# circuit.net
KiCad netlist of a schematic drawn in EAGLE
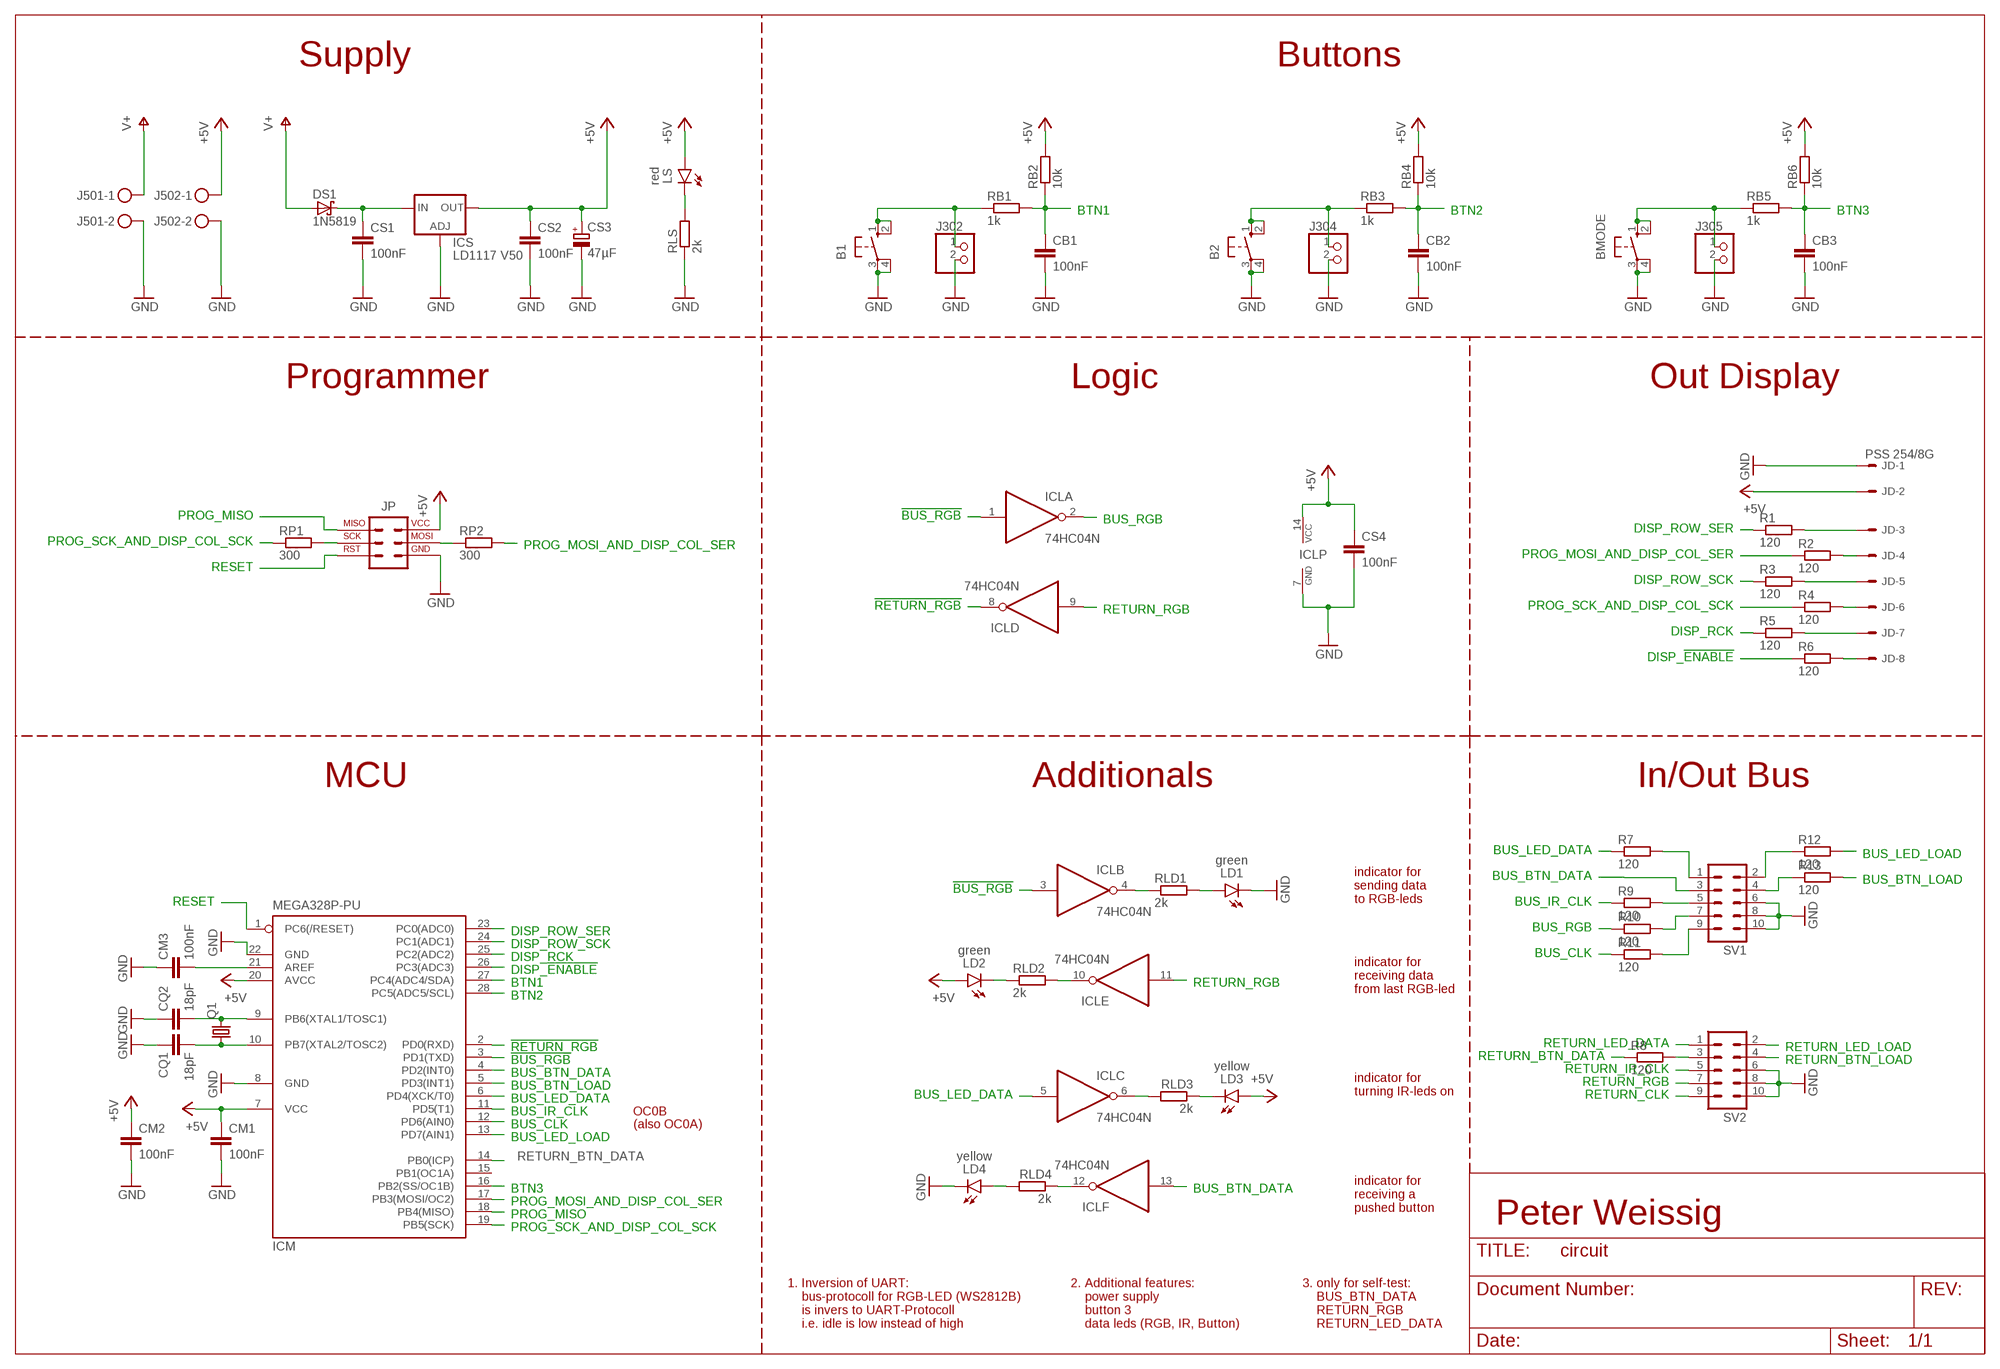
[diagram p0: schematic, sheet 1]

(export (version "E")
  (design (tool "Eeschema 10.0.6"))
  (components
    (comp (ref "B1")
      (value "10-XX")
      (footprint "eagle-import:B3F-10XX")
      (fields (field (name "MPN") "B3F-1000"))
      (libsource (lib "eagle-import") (part "10-XX"))
    )
    (comp (ref "B2")
      (value "10-XX")
      (footprint "eagle-import:B3F-10XX")
      (fields (field (name "MPN") "B3F-1000"))
      (libsource (lib "eagle-import") (part "10-XX"))
    )
    (comp (ref "BMODE")
      (value "10-XX")
      (footprint "eagle-import:B3F-10XX")
      (fields (field (name "MPN") "B3F-1000"))
      (libsource (lib "eagle-import") (part "10-XX"))
    )
    (comp (ref "CB1")
      (value "100nF")
      (footprint "eagle-import:C025-025X050")
      (libsource (lib "eagle-import") (part "C-EU025-025X050"))
    )
    (comp (ref "CB2")
      (value "100nF")
      (footprint "eagle-import:C025-025X050")
      (libsource (lib "eagle-import") (part "C-EU025-025X050"))
    )
    (comp (ref "CB3")
      (value "100nF")
      (footprint "eagle-import:C025-025X050")
      (libsource (lib "eagle-import") (part "C-EU025-025X050"))
    )
    (comp (ref "CM1")
      (value "100nF")
      (footprint "eagle-import:C025-025X050")
      (libsource (lib "eagle-import") (part "C-EU025-025X050"))
    )
    (comp (ref "CM2")
      (value "100nF")
      (footprint "eagle-import:C025-025X050")
      (libsource (lib "eagle-import") (part "C-EU025-025X050"))
    )
    (comp (ref "CM3")
      (value "100nF")
      (footprint "eagle-import:C025-025X050")
      (libsource (lib "eagle-import") (part "C-EU025-025X050"))
    )
    (comp (ref "CQ1")
      (value "18pF")
      (footprint "eagle-import:C025-025X050")
      (libsource (lib "eagle-import") (part "C-EU025-025X050"))
    )
    (comp (ref "CQ2")
      (value "18pF")
      (footprint "eagle-import:C025-025X050")
      (libsource (lib "eagle-import") (part "C-EU025-025X050"))
    )
    (comp (ref "CS1")
      (value "100nF")
      (footprint "eagle-import:C025-025X050")
      (libsource (lib "eagle-import") (part "C-EU025-025X050"))
    )
    (comp (ref "CS2")
      (value "100nF")
      (footprint "eagle-import:C025-025X050")
      (libsource (lib "eagle-import") (part "C-EU025-025X050"))
    )
    (comp (ref "CS3")
      (value "47µF")
      (footprint "eagle-import:E2-5")
      (libsource (lib "eagle-import") (part "CPOL-EUE2-5"))
    )
    (comp (ref "CS4")
      (value "100nF")
      (footprint "eagle-import:C025-025X050")
      (libsource (lib "eagle-import") (part "C-EU025-025X050"))
    )
    (comp (ref "DS1")
      (value "1N5819")
      (footprint "eagle-import:DO41-7.6")
      (libsource (lib "eagle-import") (part "1N5819-B"))
    )
    (comp (ref "ICL")
      (value "74HC04N")
      (footprint "eagle-import:DIL14")
      (libsource (lib "eagle-import") (part "7404NAC"))
    )
    (comp (ref "ICM")
      (value "MEGA328P-PU")
      (footprint "eagle-import:DIL28-3")
      (libsource (lib "eagle-import") (part "MEGA8-P"))
    )
    (comp (ref "ICS")
      (value "LD1117 V50")
      (footprint "eagle-import:TO220L1")
      (libsource (lib "eagle-import") (part "LD117A?V50"))
    )
    (comp (ref "J302")
      (value "PINHD-1X2")
      (footprint "eagle-import:1X02")
      (libsource (lib "eagle-import") (part "PINHD-1X2"))
    )
    (comp (ref "J304")
      (value "PINHD-1X2")
      (footprint "eagle-import:1X02")
      (libsource (lib "eagle-import") (part "PINHD-1X2"))
    )
    (comp (ref "J305")
      (value "PINHD-1X2")
      (footprint "eagle-import:1X02")
      (libsource (lib "eagle-import") (part "PINHD-1X2"))
    )
    (comp (ref "J501")
      (value "STECKER_SPG_2")
      (footprint "eagle-import:STECKER_SPG_2")
      (libsource (lib "eagle-import") (part "STECKER_SPG_2"))
    )
    (comp (ref "J502")
      (value "STECKER_SPG_2")
      (footprint "eagle-import:STECKER_SPG_2")
      (libsource (lib "eagle-import") (part "STECKER_SPG_2"))
    )
    (comp (ref "JD")
      (value "PSS 254/8G")
      (footprint "eagle-import:22-23-2081")
      (fields (field (name "MF") "MOLEX") (field (name "MPN") "22-23-2081"))
      (libsource (lib "eagle-import") (part "22-23-2081"))
    )
    (comp (ref "JP")
      (value "STECKER_ISP_6")
      (footprint "eagle-import:STECKER_WANNE_6")
      (libsource (lib "eagle-import") (part "STECKER_ISP_6"))
    )
    (comp (ref "LD1")
      (value "green")
      (footprint "eagle-import:LED_3MM")
      (libsource (lib "eagle-import") (part "LED-3MM"))
    )
    (comp (ref "LD2")
      (value "green")
      (footprint "eagle-import:LED_3MM")
      (libsource (lib "eagle-import") (part "LED-3MM"))
    )
    (comp (ref "LD3")
      (value "yellow")
      (footprint "eagle-import:LED_3MM")
      (libsource (lib "eagle-import") (part "LED-3MM"))
    )
    (comp (ref "LD4")
      (value "yellow")
      (footprint "eagle-import:LED_3MM")
      (libsource (lib "eagle-import") (part "LED-3MM"))
    )
    (comp (ref "LS")
      (value "red")
      (footprint "eagle-import:LED_3MM")
      (libsource (lib "eagle-import") (part "LED-3MM"))
    )
    (comp (ref "Q1")
      (value "CRYSTALHC49U70")
      (footprint "eagle-import:HC49U70")
      (libsource (lib "eagle-import") (part "CRYSTALHC49U70"))
    )
    (comp (ref "R1")
      (value "120")
      (footprint "eagle-import:R1206W")
      (libsource (lib "eagle-import") (part "R-EU_R1206W"))
    )
    (comp (ref "R2")
      (value "120")
      (footprint "eagle-import:R1206W")
      (libsource (lib "eagle-import") (part "R-EU_R1206W"))
    )
    (comp (ref "R3")
      (value "120")
      (footprint "eagle-import:R1206W")
      (libsource (lib "eagle-import") (part "R-EU_R1206W"))
    )
    (comp (ref "R4")
      (value "120")
      (footprint "eagle-import:R1206W")
      (libsource (lib "eagle-import") (part "R-EU_R1206W"))
    )
    (comp (ref "R5")
      (value "120")
      (footprint "eagle-import:R1206W")
      (libsource (lib "eagle-import") (part "R-EU_R1206W"))
    )
    (comp (ref "R6")
      (value "120")
      (footprint "eagle-import:R1206W")
      (libsource (lib "eagle-import") (part "R-EU_R1206W"))
    )
    (comp (ref "R7")
      (value "120")
      (footprint "eagle-import:R1206W")
      (libsource (lib "eagle-import") (part "R-EU_R1206W"))
    )
    (comp (ref "R8")
      (value "120")
      (footprint "eagle-import:R1206W")
      (libsource (lib "eagle-import") (part "R-EU_R1206W"))
    )
    (comp (ref "R9")
      (value "120")
      (footprint "eagle-import:R1206W")
      (libsource (lib "eagle-import") (part "R-EU_R1206W"))
    )
    (comp (ref "R10")
      (value "120")
      (footprint "eagle-import:R1206W")
      (libsource (lib "eagle-import") (part "R-EU_R1206W"))
    )
    (comp (ref "R11")
      (value "120")
      (footprint "eagle-import:R1206W")
      (libsource (lib "eagle-import") (part "R-EU_R1206W"))
    )
    (comp (ref "R12")
      (value "120")
      (footprint "eagle-import:R1206W")
      (libsource (lib "eagle-import") (part "R-EU_R1206W"))
    )
    (comp (ref "R13")
      (value "120")
      (footprint "eagle-import:R1206W")
      (libsource (lib "eagle-import") (part "R-EU_R1206W"))
    )
    (comp (ref "RB1")
      (value "1k")
      (footprint "eagle-import:0207_10")
      (libsource (lib "eagle-import") (part "R-EU_0207/10"))
    )
    (comp (ref "RB2")
      (value "10k")
      (footprint "eagle-import:0207_10")
      (libsource (lib "eagle-import") (part "R-EU_0207/10"))
    )
    (comp (ref "RB3")
      (value "1k")
      (footprint "eagle-import:0207_10")
      (libsource (lib "eagle-import") (part "R-EU_0207/10"))
    )
    (comp (ref "RB4")
      (value "10k")
      (footprint "eagle-import:0207_10")
      (libsource (lib "eagle-import") (part "R-EU_0207/10"))
    )
    (comp (ref "RB5")
      (value "1k")
      (footprint "eagle-import:0207_10")
      (libsource (lib "eagle-import") (part "R-EU_0207/10"))
    )
    (comp (ref "RB6")
      (value "10k")
      (footprint "eagle-import:0207_10")
      (libsource (lib "eagle-import") (part "R-EU_0207/10"))
    )
    (comp (ref "RLD1")
      (value "2k")
      (footprint "eagle-import:0207_10")
      (libsource (lib "eagle-import") (part "R-EU_0207/10"))
    )
    (comp (ref "RLD2")
      (value "2k")
      (footprint "eagle-import:0207_10")
      (libsource (lib "eagle-import") (part "R-EU_0207/10"))
    )
    (comp (ref "RLD3")
      (value "2k")
      (footprint "eagle-import:0207_10")
      (libsource (lib "eagle-import") (part "R-EU_0207/10"))
    )
    (comp (ref "RLD4")
      (value "2k")
      (footprint "eagle-import:0207_10")
      (libsource (lib "eagle-import") (part "R-EU_0207/10"))
    )
    (comp (ref "RLS")
      (value "2k")
      (footprint "eagle-import:0207_10")
      (libsource (lib "eagle-import") (part "R-EU_0207/10"))
    )
    (comp (ref "RP1")
      (value "300")
      (footprint "eagle-import:0207_10")
      (libsource (lib "eagle-import") (part "R-EU_0207/10"))
    )
    (comp (ref "RP2")
      (value "300")
      (footprint "eagle-import:0207_10")
      (libsource (lib "eagle-import") (part "R-EU_0207/10"))
    )
    (comp (ref "SV1")
      (value "ML10")
      (footprint "eagle-import:ML10")
      (libsource (lib "eagle-import") (part "ML10"))
    )
    (comp (ref "SV2")
      (value "ML10")
      (footprint "eagle-import:ML10")
      (libsource (lib "eagle-import") (part "ML10"))
    )
  )
  (nets
    (net (code "1") (name "+5V") (class "Default")
      (node (ref "CM1") (pin "1") (pinfunction "1_1") (pintype "passive"))
      (node (ref "CM2") (pin "1") (pinfunction "1_1") (pintype "passive"))
      (node (ref "CS2") (pin "1") (pinfunction "1_1") (pintype "passive"))
      (node (ref "CS3") (pin "+") (pinfunction "+_+") (pintype "passive"))
      (node (ref "CS4") (pin "1") (pinfunction "1_1") (pintype "passive"))
      (node (ref "ICL") (pin "14") (pinfunction "VCC_14") (pintype "power_in"))
      (node (ref "ICM") (pin "20") (pinfunction "AVCC_20") (pintype "power_in"))
      (node (ref "ICM") (pin "7") (pinfunction "VCC_7") (pintype "power_in"))
      (node (ref "ICS") (pin "2") (pinfunction "OUT_2") (pintype "passive"))
      (node (ref "J502") (pin "1") (pinfunction "KL_1") (pintype "passive"))
      (node (ref "JD") (pin "2") (pinfunction "S_2") (pintype "passive"))
      (node (ref "JP") (pin "2") (pinfunction "2_VCC_2") (pintype "passive"))
      (node (ref "LD2") (pin "A") (pinfunction "A_A") (pintype "passive"))
      (node (ref "LD3") (pin "A") (pinfunction "A_A") (pintype "passive"))
      (node (ref "LS") (pin "A") (pinfunction "A_A") (pintype "passive"))
      (node (ref "RB2") (pin "2") (pinfunction "2_2") (pintype "passive"))
      (node (ref "RB4") (pin "2") (pinfunction "2_2") (pintype "passive"))
      (node (ref "RB6") (pin "2") (pinfunction "2_2") (pintype "passive"))
    )
    (net (code "2") (name "/BTN1") (class "Default")
      (node (ref "CB1") (pin "1") (pinfunction "1_1") (pintype "passive"))
      (node (ref "ICM") (pin "27") (pinfunction "PC4(ADC4/SDA)_27") (pintype "bidirectional"))
      (node (ref "RB1") (pin "2") (pinfunction "2_2") (pintype "passive"))
      (node (ref "RB2") (pin "1") (pinfunction "1_1") (pintype "passive"))
    )
    (net (code "3") (name "/BTN2") (class "Default")
      (node (ref "CB2") (pin "1") (pinfunction "1_1") (pintype "passive"))
      (node (ref "ICM") (pin "28") (pinfunction "PC5(ADC5/SCL)_28") (pintype "bidirectional"))
      (node (ref "RB3") (pin "2") (pinfunction "2_2") (pintype "passive"))
      (node (ref "RB4") (pin "1") (pinfunction "1_1") (pintype "passive"))
    )
    (net (code "4") (name "/BTN3") (class "Default")
      (node (ref "CB3") (pin "1") (pinfunction "1_1") (pintype "passive"))
      (node (ref "ICM") (pin "16") (pinfunction "PB2(SS/OC1B)_16") (pintype "bidirectional"))
      (node (ref "RB5") (pin "2") (pinfunction "2_2") (pintype "passive"))
      (node (ref "RB6") (pin "1") (pinfunction "1_1") (pintype "passive"))
    )
    (net (code "5") (name "/BUS_BTN_DATA") (class "Default")
      (node (ref "ICL") (pin "13") (pinfunction "I_13") (pintype "input"))
      (node (ref "ICM") (pin "4") (pinfunction "PD2(INT0)_4") (pintype "bidirectional"))
      (node (ref "SV1") (pin "3") (pinfunction "3_3") (pintype "passive"))
    )
    (net (code "6") (name "/BUS_BTN_LOAD") (class "Default")
      (node (ref "ICM") (pin "5") (pinfunction "PD3(INT1)_5") (pintype "bidirectional"))
      (node (ref "R13") (pin "2") (pinfunction "2_2") (pintype "passive"))
    )
    (net (code "7") (name "/BUS_CLK") (class "Default")
      (node (ref "ICM") (pin "12") (pinfunction "PD6(AIN0)_12") (pintype "bidirectional"))
      (node (ref "R11") (pin "1") (pinfunction "1_1") (pintype "passive"))
    )
    (net (code "8") (name "/BUS_IR_CLK") (class "Default")
      (node (ref "ICM") (pin "11") (pinfunction "PD5(T1)_11") (pintype "bidirectional"))
      (node (ref "R9") (pin "1") (pinfunction "1_1") (pintype "passive"))
    )
    (net (code "9") (name "/BUS_LED_DATA") (class "Default")
      (node (ref "ICL") (pin "5") (pinfunction "I_5") (pintype "input"))
      (node (ref "ICM") (pin "6") (pinfunction "PD4(XCK/T0)_6") (pintype "bidirectional"))
      (node (ref "R7") (pin "1") (pinfunction "1_1") (pintype "passive"))
    )
    (net (code "10") (name "/BUS_LED_LOAD") (class "Default")
      (node (ref "ICM") (pin "13") (pinfunction "PD7(AIN1)_13") (pintype "bidirectional"))
      (node (ref "R12") (pin "2") (pinfunction "2_2") (pintype "passive"))
    )
    (net (code "11") (name "/BUS_RGB") (class "Default")
      (node (ref "ICL") (pin "2") (pinfunction "O_2") (pintype "output"))
      (node (ref "R10") (pin "1") (pinfunction "1_1") (pintype "passive"))
    )
    (net (code "12") (name "/DISP_RCK") (class "Default")
      (node (ref "ICM") (pin "25") (pinfunction "PC2(ADC2)_25") (pintype "bidirectional"))
      (node (ref "R5") (pin "1") (pinfunction "1_1") (pintype "passive"))
    )
    (net (code "13") (name "/DISP_ROW_SCK") (class "Default")
      (node (ref "ICM") (pin "24") (pinfunction "PC1(ADC1)_24") (pintype "bidirectional"))
      (node (ref "R3") (pin "1") (pinfunction "1_1") (pintype "passive"))
    )
    (net (code "14") (name "/DISP_ROW_SER") (class "Default")
      (node (ref "ICM") (pin "23") (pinfunction "PC0(ADC0)_23") (pintype "bidirectional"))
      (node (ref "R1") (pin "1") (pinfunction "1_1") (pintype "passive"))
    )
    (net (code "15") (name "/DISP_~{ENABLE}") (class "Default")
      (node (ref "ICM") (pin "26") (pinfunction "PC3(ADC3)_26") (pintype "bidirectional"))
      (node (ref "R6") (pin "1") (pinfunction "1_1") (pintype "passive"))
    )
    (net (code "16") (name "/PROG_MISO") (class "Default")
      (node (ref "ICM") (pin "18") (pinfunction "PB4(MISO)_18") (pintype "bidirectional"))
      (node (ref "JP") (pin "1") (pinfunction "1_MISO_1") (pintype "passive"))
    )
    (net (code "17") (name "/PROG_MOSI_AND_DISP_COL_SER") (class "Default")
      (node (ref "ICM") (pin "17") (pinfunction "PB3(MOSI/OC2)_17") (pintype "bidirectional"))
      (node (ref "R2") (pin "1") (pinfunction "1_1") (pintype "passive"))
      (node (ref "RP2") (pin "2") (pinfunction "2_2") (pintype "passive"))
    )
    (net (code "18") (name "/PROG_SCK_AND_DISP_COL_SCK") (class "Default")
      (node (ref "ICM") (pin "19") (pinfunction "PB5(SCK)_19") (pintype "bidirectional"))
      (node (ref "R4") (pin "1") (pinfunction "1_1") (pintype "passive"))
      (node (ref "RP1") (pin "1") (pinfunction "1_1") (pintype "passive"))
    )
    (net (code "19") (name "/RESET") (class "Default")
      (node (ref "ICM") (pin "1") (pinfunction "PC6(/RESET)_1") (pintype "bidirectional"))
      (node (ref "JP") (pin "5") (pinfunction "5_RST_5") (pintype "passive"))
    )
    (net (code "20") (name "/RETURN_BTN_DATA") (class "Default")
      (node (ref "ICM") (pin "14") (pinfunction "PB0(ICP)_14") (pintype "bidirectional"))
      (node (ref "R8") (pin "1") (pinfunction "1_1") (pintype "passive"))
    )
    (net (code "21") (name "/RETURN_BTN_LOAD") (class "Default")
      (node (ref "SV2") (pin "4") (pinfunction "4_4") (pintype "passive"))
    )
    (net (code "22") (name "/RETURN_CLK") (class "Default")
      (node (ref "SV2") (pin "9") (pinfunction "9_9") (pintype "passive"))
    )
    (net (code "23") (name "/RETURN_IR_CLK") (class "Default")
      (node (ref "SV2") (pin "5") (pinfunction "5_5") (pintype "passive"))
    )
    (net (code "24") (name "/RETURN_LED_DATA") (class "Default")
      (node (ref "SV2") (pin "1") (pinfunction "1_1") (pintype "passive"))
    )
    (net (code "25") (name "/RETURN_LED_LOAD") (class "Default")
      (node (ref "SV2") (pin "2") (pinfunction "2_2") (pintype "passive"))
    )
    (net (code "26") (name "/RETURN_RGB") (class "Default")
      (node (ref "ICL") (pin "11") (pinfunction "I_11") (pintype "input"))
      (node (ref "ICL") (pin "9") (pinfunction "I_9") (pintype "input"))
      (node (ref "SV2") (pin "7") (pinfunction "7_7") (pintype "passive"))
    )
    (net (code "27") (name "/~{BUS_RGB}") (class "Default")
      (node (ref "ICL") (pin "1") (pinfunction "I_1") (pintype "input"))
      (node (ref "ICL") (pin "3") (pinfunction "I_3") (pintype "input"))
      (node (ref "ICM") (pin "3") (pinfunction "PD1(TXD)_3") (pintype "bidirectional"))
    )
    (net (code "28") (name "/~{RETURN_RGB}") (class "Default")
      (node (ref "ICL") (pin "8") (pinfunction "O_8") (pintype "output"))
      (node (ref "ICM") (pin "2") (pinfunction "PD0(RXD)_2") (pintype "bidirectional"))
    )
    (net (code "29") (name "GND") (class "Default")
      (node (ref "B1") (pin "3") (pinfunction "P_3") (pintype "passive"))
      (node (ref "B1") (pin "4") (pinfunction "P1_4") (pintype "passive"))
      (node (ref "B2") (pin "3") (pinfunction "P_3") (pintype "passive"))
      (node (ref "B2") (pin "4") (pinfunction "P1_4") (pintype "passive"))
      (node (ref "BMODE") (pin "3") (pinfunction "P_3") (pintype "passive"))
      (node (ref "BMODE") (pin "4") (pinfunction "P1_4") (pintype "passive"))
      (node (ref "CB1") (pin "2") (pinfunction "2_2") (pintype "passive"))
      (node (ref "CB2") (pin "2") (pinfunction "2_2") (pintype "passive"))
      (node (ref "CB3") (pin "2") (pinfunction "2_2") (pintype "passive"))
      (node (ref "CM1") (pin "2") (pinfunction "2_2") (pintype "passive"))
      (node (ref "CM2") (pin "2") (pinfunction "2_2") (pintype "passive"))
      (node (ref "CM3") (pin "1") (pinfunction "1_1") (pintype "passive"))
      (node (ref "CQ1") (pin "1") (pinfunction "1_1") (pintype "passive"))
      (node (ref "CQ2") (pin "1") (pinfunction "1_1") (pintype "passive"))
      (node (ref "CS1") (pin "2") (pinfunction "2_2") (pintype "passive"))
      (node (ref "CS2") (pin "2") (pinfunction "2_2") (pintype "passive"))
      (node (ref "CS3") (pin "-") (pinfunction "-_-") (pintype "passive"))
      (node (ref "CS4") (pin "2") (pinfunction "2_2") (pintype "passive"))
      (node (ref "ICL") (pin "7") (pinfunction "GND_7") (pintype "power_in"))
      (node (ref "ICM") (pin "22") (pinfunction "GND_22") (pintype "power_in"))
      (node (ref "ICM") (pin "8") (pinfunction "GND_8") (pintype "power_in"))
      (node (ref "ICS") (pin "1") (pinfunction "ADJ_1") (pintype "input"))
      (node (ref "J302") (pin "2") (pinfunction "2_2") (pintype "passive"))
      (node (ref "J304") (pin "2") (pinfunction "2_2") (pintype "passive"))
      (node (ref "J305") (pin "2") (pinfunction "2_2") (pintype "passive"))
      (node (ref "J501") (pin "2") (pinfunction "KL_2") (pintype "passive"))
      (node (ref "J502") (pin "2") (pinfunction "KL_2") (pintype "passive"))
      (node (ref "JD") (pin "1") (pinfunction "S_1") (pintype "passive"))
      (node (ref "JP") (pin "6") (pinfunction "6_GND_6") (pintype "passive"))
      (node (ref "LD1") (pin "K") (pinfunction "C_K") (pintype "passive"))
      (node (ref "LD4") (pin "K") (pinfunction "C_K") (pintype "passive"))
      (node (ref "RLS") (pin "1") (pinfunction "1_1") (pintype "passive"))
      (node (ref "SV1") (pin "10") (pinfunction "10_10") (pintype "passive"))
      (node (ref "SV1") (pin "6") (pinfunction "6_6") (pintype "passive"))
      (node (ref "SV1") (pin "8") (pinfunction "8_8") (pintype "passive"))
      (node (ref "SV2") (pin "10") (pinfunction "10_10") (pintype "passive"))
      (node (ref "SV2") (pin "6") (pinfunction "6_6") (pintype "passive"))
      (node (ref "SV2") (pin "8") (pinfunction "8_8") (pintype "passive"))
    )
    (net (code "30") (name "Net-(B1-S)") (class "Default")
      (node (ref "B1") (pin "1") (pinfunction "S_1") (pintype "passive"))
      (node (ref "B1") (pin "2") (pinfunction "S1_2") (pintype "passive"))
      (node (ref "J302") (pin "1") (pinfunction "1_1") (pintype "passive"))
      (node (ref "RB1") (pin "1") (pinfunction "1_1") (pintype "passive"))
    )
    (net (code "31") (name "Net-(B2-S)") (class "Default")
      (node (ref "B2") (pin "1") (pinfunction "S_1") (pintype "passive"))
      (node (ref "B2") (pin "2") (pinfunction "S1_2") (pintype "passive"))
      (node (ref "J304") (pin "1") (pinfunction "1_1") (pintype "passive"))
      (node (ref "RB3") (pin "1") (pinfunction "1_1") (pintype "passive"))
    )
    (net (code "32") (name "Net-(BMODE-S)") (class "Default")
      (node (ref "BMODE") (pin "1") (pinfunction "S_1") (pintype "passive"))
      (node (ref "BMODE") (pin "2") (pinfunction "S1_2") (pintype "passive"))
      (node (ref "J305") (pin "1") (pinfunction "1_1") (pintype "passive"))
      (node (ref "RB5") (pin "1") (pinfunction "1_1") (pintype "passive"))
    )
    (net (code "33") (name "Net-(ICLB-O)") (class "Default")
      (node (ref "ICL") (pin "4") (pinfunction "O_4") (pintype "output"))
      (node (ref "RLD1") (pin "1") (pinfunction "1_1") (pintype "passive"))
    )
    (net (code "34") (name "Net-(ICLC-O)") (class "Default")
      (node (ref "ICL") (pin "6") (pinfunction "O_6") (pintype "output"))
      (node (ref "RLD3") (pin "2") (pinfunction "2_2") (pintype "passive"))
    )
    (net (code "35") (name "Net-(ICLE-O)") (class "Default")
      (node (ref "ICL") (pin "10") (pinfunction "O_10") (pintype "output"))
      (node (ref "RLD2") (pin "2") (pinfunction "2_2") (pintype "passive"))
    )
    (net (code "36") (name "Net-(ICLF-O)") (class "Default")
      (node (ref "ICL") (pin "12") (pinfunction "O_12") (pintype "output"))
      (node (ref "RLD4") (pin "1") (pinfunction "1_1") (pintype "passive"))
    )
    (net (code "37") (name "Net-(ICM-AREF)") (class "Default")
      (node (ref "CM3") (pin "2") (pinfunction "2_2") (pintype "passive"))
      (node (ref "ICM") (pin "21") (pinfunction "AREF_21") (pintype "passive"))
    )
    (net (code "38") (name "Net-(ICM-PB6(XTAL1{slash}TOSC1))") (class "Default")
      (node (ref "CQ2") (pin "2") (pinfunction "2_2") (pintype "passive"))
      (node (ref "ICM") (pin "9") (pinfunction "PB6(XTAL1/TOSC1)_9") (pintype "bidirectional"))
      (node (ref "Q1") (pin "2") (pinfunction "2_2") (pintype "passive"))
    )
    (net (code "39") (name "Net-(ICM-PB7(XTAL2{slash}TOSC2))") (class "Default")
      (node (ref "CQ1") (pin "2") (pinfunction "2_2") (pintype "passive"))
      (node (ref "ICM") (pin "10") (pinfunction "PB7(XTAL2/TOSC2)_10") (pintype "bidirectional"))
      (node (ref "Q1") (pin "1") (pinfunction "1_1") (pintype "passive"))
    )
    (net (code "40") (name "Net-(ICS-IN)") (class "Default")
      (node (ref "CS1") (pin "1") (pinfunction "1_1") (pintype "passive"))
      (node (ref "DS1") (pin "C") (pinfunction "C_C") (pintype "passive"))
      (node (ref "ICS") (pin "3") (pinfunction "IN_3") (pintype "input"))
    )
    (net (code "41") (name "Net-(JDC-S)") (class "Default")
      (node (ref "JD") (pin "3") (pinfunction "S_3") (pintype "passive"))
      (node (ref "R1") (pin "2") (pinfunction "2_2") (pintype "passive"))
    )
    (net (code "42") (name "Net-(JDD-S)") (class "Default")
      (node (ref "JD") (pin "4") (pinfunction "S_4") (pintype "passive"))
      (node (ref "R2") (pin "2") (pinfunction "2_2") (pintype "passive"))
    )
    (net (code "43") (name "Net-(JDE-S)") (class "Default")
      (node (ref "JD") (pin "5") (pinfunction "S_5") (pintype "passive"))
      (node (ref "R3") (pin "2") (pinfunction "2_2") (pintype "passive"))
    )
    (net (code "44") (name "Net-(JDF-S)") (class "Default")
      (node (ref "JD") (pin "6") (pinfunction "S_6") (pintype "passive"))
      (node (ref "R4") (pin "2") (pinfunction "2_2") (pintype "passive"))
    )
    (net (code "45") (name "Net-(JDG-S)") (class "Default")
      (node (ref "JD") (pin "7") (pinfunction "S_7") (pintype "passive"))
      (node (ref "R5") (pin "2") (pinfunction "2_2") (pintype "passive"))
    )
    (net (code "46") (name "Net-(JDH-S)") (class "Default")
      (node (ref "JD") (pin "8") (pinfunction "S_8") (pintype "passive"))
      (node (ref "R6") (pin "2") (pinfunction "2_2") (pintype "passive"))
    )
    (net (code "47") (name "Net-(JP-3_SCK)") (class "Default")
      (node (ref "JP") (pin "3") (pinfunction "3_SCK_3") (pintype "passive"))
      (node (ref "RP1") (pin "2") (pinfunction "2_2") (pintype "passive"))
    )
    (net (code "48") (name "Net-(JP-4_MOSI)") (class "Default")
      (node (ref "JP") (pin "4") (pinfunction "4_MOSI_4") (pintype "passive"))
      (node (ref "RP2") (pin "1") (pinfunction "1_1") (pintype "passive"))
    )
    (net (code "49") (name "Net-(LD1-PadA)") (class "Default")
      (node (ref "LD1") (pin "A") (pinfunction "A_A") (pintype "passive"))
      (node (ref "RLD1") (pin "2") (pinfunction "2_2") (pintype "passive"))
    )
    (net (code "50") (name "Net-(LD2-C)") (class "Default")
      (node (ref "LD2") (pin "K") (pinfunction "C_K") (pintype "passive"))
      (node (ref "RLD2") (pin "1") (pinfunction "1_1") (pintype "passive"))
    )
    (net (code "51") (name "Net-(LD3-C)") (class "Default")
      (node (ref "LD3") (pin "K") (pinfunction "C_K") (pintype "passive"))
      (node (ref "RLD3") (pin "1") (pinfunction "1_1") (pintype "passive"))
    )
    (net (code "52") (name "Net-(LD4-PadA)") (class "Default")
      (node (ref "LD4") (pin "A") (pinfunction "A_A") (pintype "passive"))
      (node (ref "RLD4") (pin "2") (pinfunction "2_2") (pintype "passive"))
    )
    (net (code "53") (name "Net-(LS-C)") (class "Default")
      (node (ref "LS") (pin "K") (pinfunction "C_K") (pintype "passive"))
      (node (ref "RLS") (pin "2") (pinfunction "2_2") (pintype "passive"))
    )
    (net (code "54") (name "Net-(R7-Pad2)") (class "Default")
      (node (ref "R7") (pin "2") (pinfunction "2_2") (pintype "passive"))
      (node (ref "SV1") (pin "1") (pinfunction "1_1") (pintype "passive"))
    )
    (net (code "55") (name "Net-(R8-Pad2)") (class "Default")
      (node (ref "R8") (pin "2") (pinfunction "2_2") (pintype "passive"))
      (node (ref "SV2") (pin "3") (pinfunction "3_3") (pintype "passive"))
    )
    (net (code "56") (name "Net-(R9-Pad2)") (class "Default")
      (node (ref "R9") (pin "2") (pinfunction "2_2") (pintype "passive"))
      (node (ref "SV1") (pin "5") (pinfunction "5_5") (pintype "passive"))
    )
    (net (code "57") (name "Net-(R10-Pad2)") (class "Default")
      (node (ref "R10") (pin "2") (pinfunction "2_2") (pintype "passive"))
      (node (ref "SV1") (pin "7") (pinfunction "7_7") (pintype "passive"))
    )
    (net (code "58") (name "Net-(R11-Pad2)") (class "Default")
      (node (ref "R11") (pin "2") (pinfunction "2_2") (pintype "passive"))
      (node (ref "SV1") (pin "9") (pinfunction "9_9") (pintype "passive"))
    )
    (net (code "59") (name "Net-(R12-Pad1)") (class "Default")
      (node (ref "R12") (pin "1") (pinfunction "1_1") (pintype "passive"))
      (node (ref "SV1") (pin "2") (pinfunction "2_2") (pintype "passive"))
    )
    (net (code "60") (name "Net-(R13-Pad1)") (class "Default")
      (node (ref "R13") (pin "1") (pinfunction "1_1") (pintype "passive"))
      (node (ref "SV1") (pin "4") (pinfunction "4_4") (pintype "passive"))
    )
    (net (code "61") (name "V+") (class "Default")
      (node (ref "DS1") (pin "A") (pinfunction "A_A") (pintype "passive"))
      (node (ref "J501") (pin "1") (pinfunction "KL_1") (pintype "passive"))
    )
    (net (code "62") (name "unconnected-(ICM-PB1(OC1A)-Pad15)") (class "Default")
      (node (ref "ICM") (pin "15") (pinfunction "PB1(OC1A)_15") (pintype "bidirectional"))
    )
  )
)
